# 16VPow.net
KiCad netlist of a schematic drawn in Altium Designer
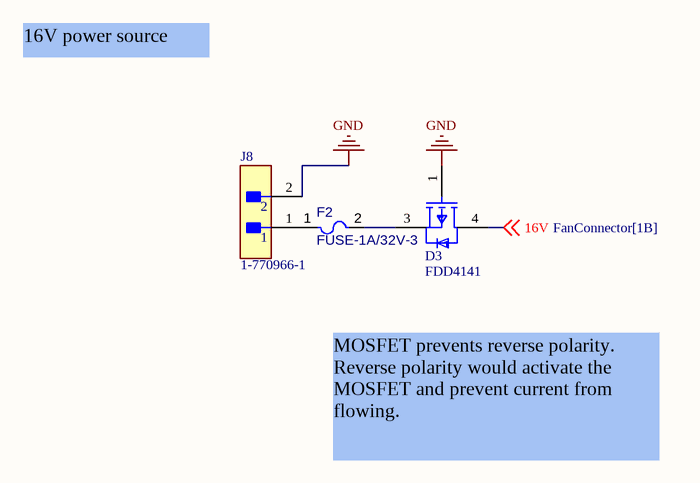
[diagram p0: 16VPow.SchDoc]

(export (version "E")
  (design (tool "Eeschema 10.0.6"))
  (components
    (comp (ref "D3")
      (value "FDD4141")
      (footprint "FP-369AS-MFG")
      (description "MOSFET P-CH 40V 10.8A DPAK")
      (fields
        (field (name "OCTOPART") "https://octopart.com/fdd4141-on+semiconductor-84325802")
        (field (name "MANUFACTURER") "ON Semiconductor")
      )
      (libsource (lib "Altium Content Vault") (part "ec195c925100855187fe8c06440c3e1"))
    )
    (comp (ref "F2")
      (value "FUSE-1A/32V-3")
      (footprint "LFUS-467_V")
      (description "Fast Acting Fuse, 1 A, 32 V, -55 to 90 degC, 2-Pin SMD, RoHS, Tape and Reel")
      (libsource (lib "Alt_ium Course") (part "CMP-001-0019-1"))
    )
    (comp (ref "J8")
      (value "1-770966-1")
      (footprint "FP-1-770966-1-MFG")
      (description "CONN HEADER R/A 2POS 4.14MM")
      (fields
        (field (name "OCTOPART") "https://octopart.com/1-770966-1-te+connectivity-46506767")
        (field (name "MANUFACTURER") "TE")
      )
      (libsource (lib "Altium Content Vault") (part "3bc925449376181038e59eaffc5286c"))
    )
  )
  (nets
    (net (code "1") (name "16V") (class "Default")
      (node (ref "D3") (pin "4") (pinfunction "D_4") (pintype "passive"))
    )
    (net (code "2") (name "GND") (class "Default")
      (node (ref "D3") (pin "1") (pinfunction "G_1") (pintype "passive"))
      (node (ref "J8") (pin "2") (pinfunction "2_2") (pintype "passive"))
    )
    (net (code "3") (name "Net-(D3-S)") (class "Default")
      (node (ref "D3") (pin "3") (pinfunction "S_3") (pintype "passive"))
      (node (ref "F2") (pin "2") (pinfunction "2_2") (pintype "passive"))
    )
    (net (code "4") (name "Net-(F2-Pad1)") (class "Default")
      (node (ref "F2") (pin "1") (pinfunction "1_1") (pintype "passive"))
      (node (ref "J8") (pin "1") (pinfunction "1_1") (pintype "passive"))
    )
  )
)
